# Ambient_Light.net
KiCad netlist of a schematic drawn in Altium Designer
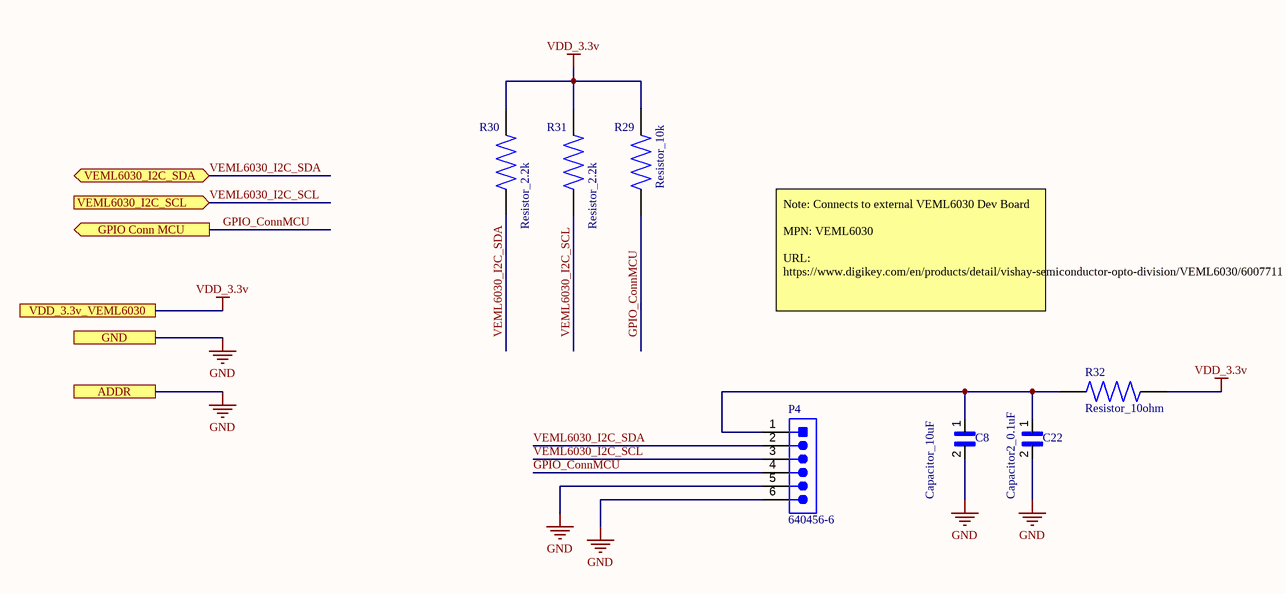
[diagram p0: Ambient_Light.SchDoc]

(export (version "E")
  (design (tool "Eeschema 10.0.6"))
  (components
    (comp (ref "C8")
      (value "Capacitor_10uF")
      (footprint "Capacitor_10uF")
      (description "0805 35 V 10 uF ±10% Tolerance X5R Multilayer Ceramic Capacitor")
      (libsource (lib "Schematic_Lib") (part "Capacitor_10uF"))
    )
    (comp (ref "C22")
      (value "Capacitor2_0.1uF")
      (footprint "Capacitor2_0.1uF")
      (description "Cap Ceramic 0.1uF 16V X5R 10% SMD 0402 85°C Paper T/R")
      (fields
        (field (name "MANUFACTURER") "KEMET")
        (field (name "MANUFACTURER PART NUMBER") "C0402C104K4PACTU")
      )
      (libsource (lib "Schematic_Lib") (part "Capacitor2_0.1uF"))
    )
    (comp (ref "P4")
      (value "640456-6")
      (footprint "TECO-640456-6_V")
      (fields (field (name "MANUFACTURER") "TE Connectivity"))
      (libsource (lib "Altium Content Vault") (part "CN-1P-M-R6"))
    )
    (comp (ref "R29")
      (value "Resistor_10k")
      (footprint "Resistor_10k")
      (description "Res Thin Film 0805 10K Ohm 1% 1/10W ±50ppm/°C Molded SMD SMD Paper T/R")
      (fields
        (field (name "MANUFACTURER") "TE Connectivity Neohm")
        (field (name "MANUFACTURER PART NUMBER") "CPF0805F10KC1")
      )
      (libsource (lib "Schematic_Lib") (part "Resistor_10k"))
    )
    (comp (ref "R30")
      (value "Resistor_2.2k")
      (footprint "Resistor_2.2k")
      (description "Res Thick Film 0805 2.2K Ohm 5% 1/3W ±100ppm/°C Molded SMD SMD T/R")
      (fields
        (field (name "MANUFACTURER") "TE Connectivity Holsworthy")
        (field (name "MANUFACTURER PART NUMBER") "CRGH0805J2K2")
      )
      (libsource (lib "Schematic_Lib") (part "Resistor_2.2k"))
    )
    (comp (ref "R31")
      (value "Resistor_2.2k")
      (footprint "Resistor_2.2k")
      (description "Res Thick Film 0805 2.2K Ohm 5% 1/3W ±100ppm/°C Molded SMD SMD T/R")
      (fields
        (field (name "MANUFACTURER") "TE Connectivity Holsworthy")
        (field (name "MANUFACTURER PART NUMBER") "CRGH0805J2K2")
      )
      (libsource (lib "Schematic_Lib") (part "Resistor_2.2k"))
    )
    (comp (ref "R32")
      (value "Resistor_10ohm")
      (footprint "Resistor_10ohm")
      (description "RES TF 1/10W 10 OHM 1% 0603")
      (fields
        (field (name "MANUFACTURER") "Yageo")
        (field (name "MANUFACTURER PART NUMBER") "RT0603DRE0710RL")
      )
      (libsource (lib "Schematic_Lib") (part "Resistor_10ohm"))
    )
  )
  (nets
    (net (code "1") (name "/GPIO_ConnMCU") (class "Default")
      (node (ref "P4") (pin "4") (pinfunction "4_4") (pintype "passive"))
      (node (ref "R29") (pin "1") (pinfunction "1_1") (pintype "passive"))
    )
    (net (code "2") (name "/VEML6030_I2C_SCL") (class "Default")
      (node (ref "P4") (pin "3") (pinfunction "3_3") (pintype "passive"))
      (node (ref "R31") (pin "1") (pinfunction "1_1") (pintype "passive"))
    )
    (net (code "3") (name "/VEML6030_I2C_SDA") (class "Default")
      (node (ref "P4") (pin "2") (pinfunction "2_2") (pintype "passive"))
      (node (ref "R30") (pin "1") (pinfunction "1_1") (pintype "passive"))
    )
    (net (code "4") (name "GND") (class "Default")
      (node (ref "C22") (pin "2") (pinfunction "2_2") (pintype "passive"))
      (node (ref "C8") (pin "2") (pinfunction "2_2") (pintype "passive"))
      (node (ref "P4") (pin "5") (pinfunction "5_5") (pintype "passive"))
      (node (ref "P4") (pin "6") (pinfunction "6_6") (pintype "passive"))
    )
    (net (code "5") (name "Net-(C22-Pad1)") (class "Default")
      (node (ref "C22") (pin "1") (pinfunction "1_1") (pintype "passive"))
      (node (ref "C8") (pin "1") (pinfunction "1_1") (pintype "passive"))
      (node (ref "P4") (pin "1") (pinfunction "1_1") (pintype "passive"))
      (node (ref "R32") (pin "1") (pinfunction "1_1") (pintype "passive"))
    )
    (net (code "6") (name "VDD_3.3v") (class "Default")
      (node (ref "R29") (pin "2") (pinfunction "2_2") (pintype "passive"))
      (node (ref "R30") (pin "2") (pinfunction "2_2") (pintype "passive"))
      (node (ref "R31") (pin "2") (pinfunction "2_2") (pintype "passive"))
      (node (ref "R32") (pin "2") (pinfunction "2_2") (pintype "passive"))
    )
  )
)
